# RGB_driver_main.net
KiCad netlist of a schematic drawn in EAGLE
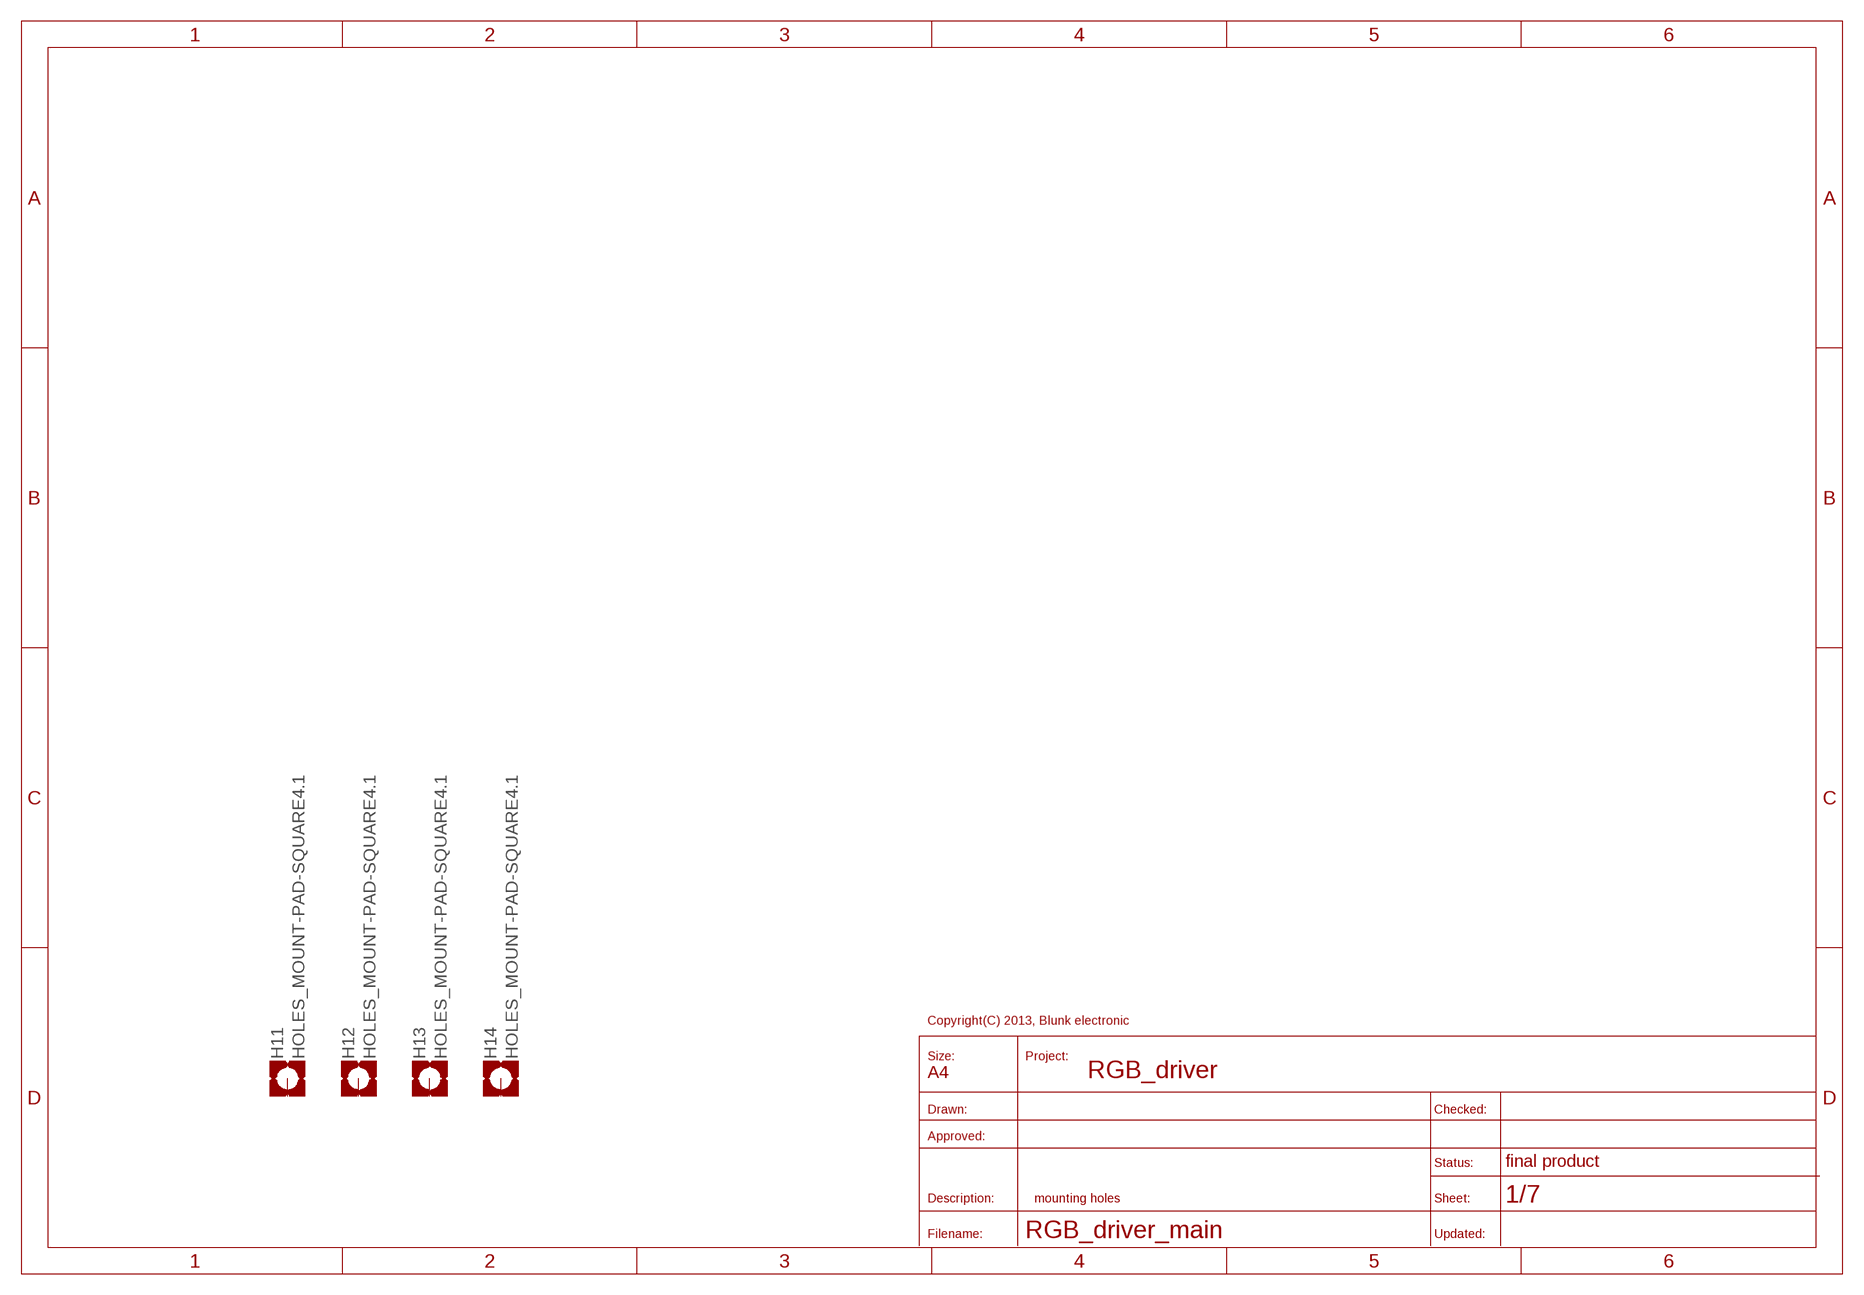
[diagram p0: schematic, sheet 1]
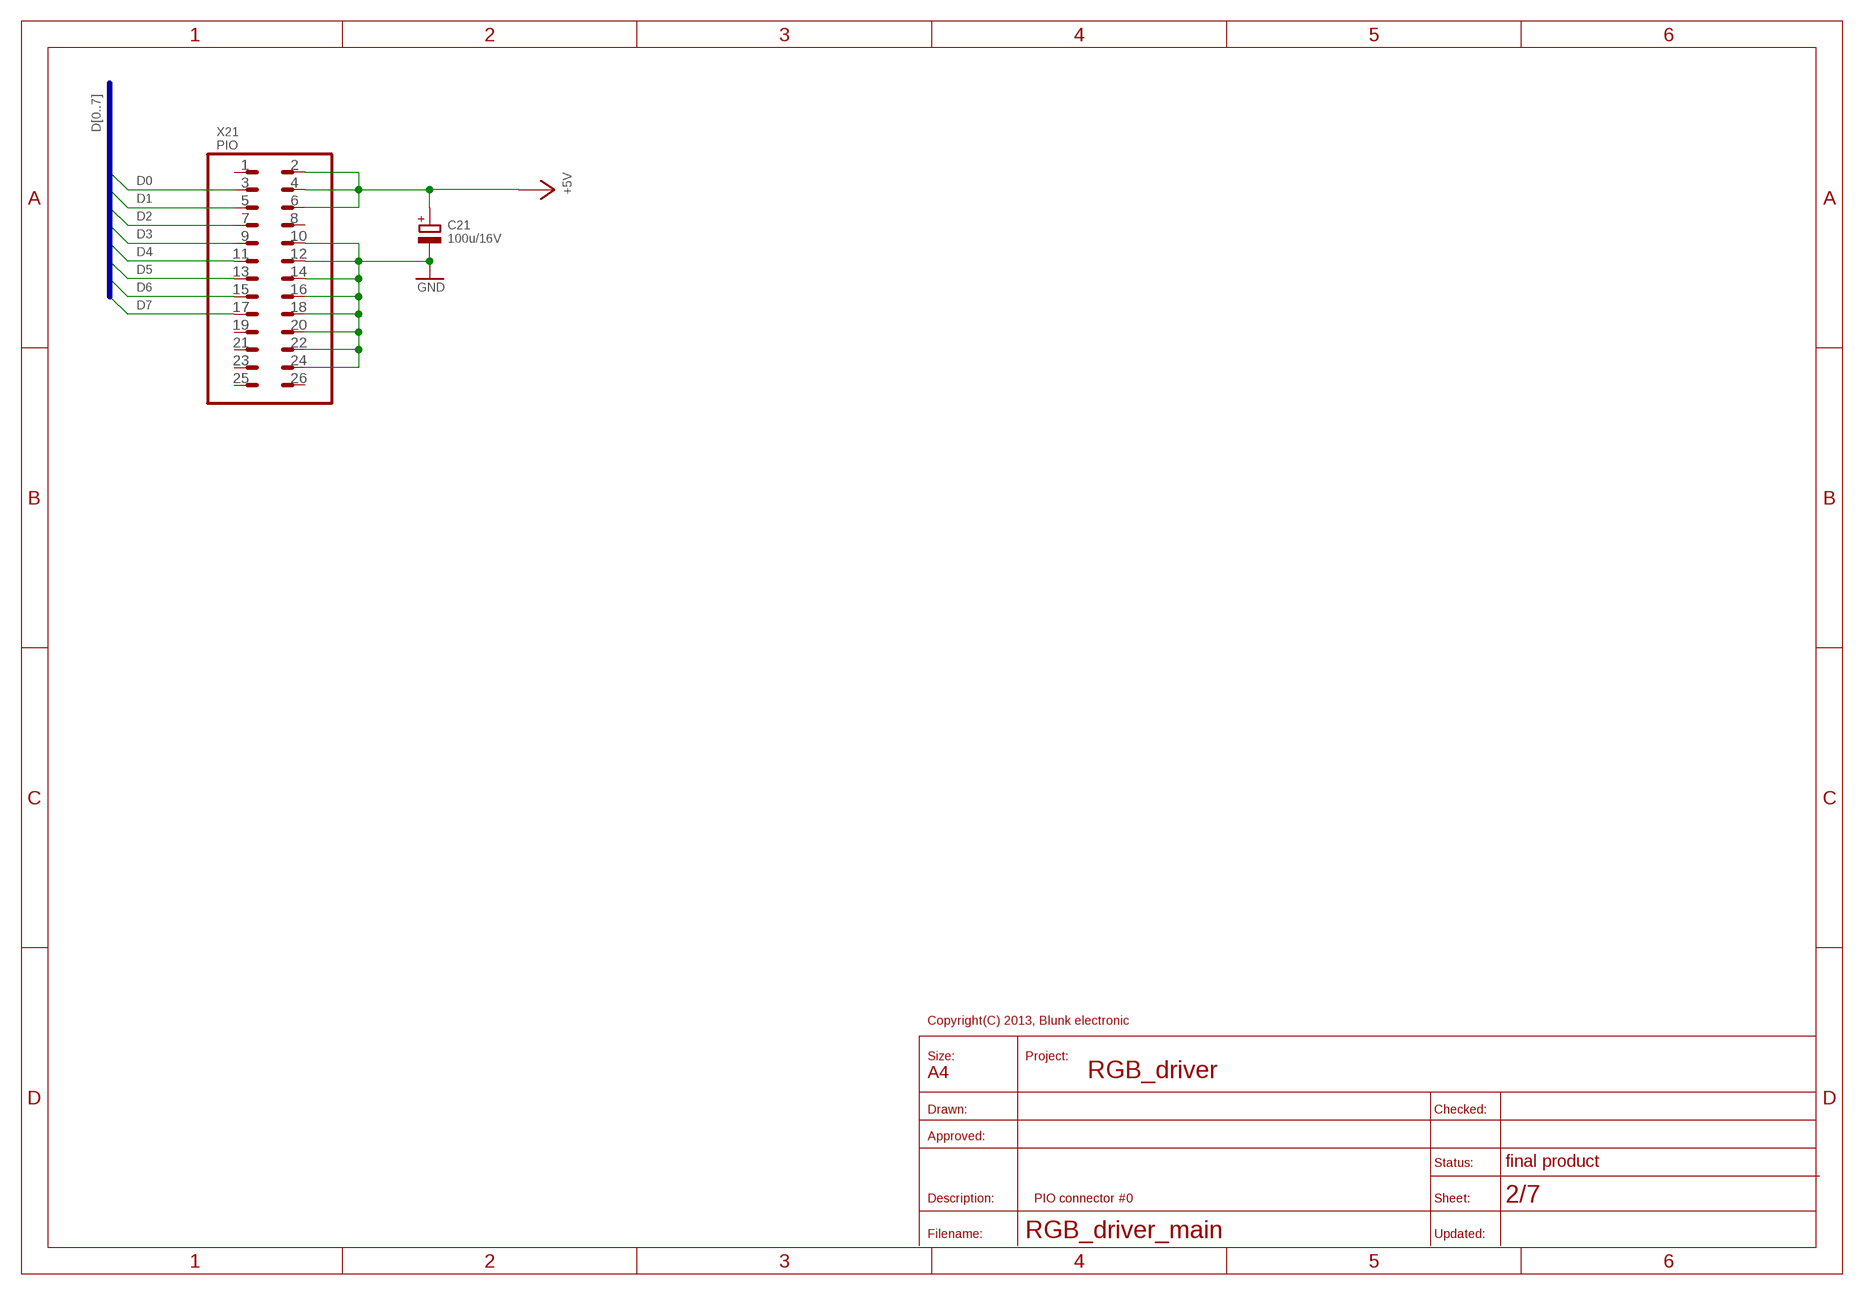
[diagram p1: schematic, sheet 2]
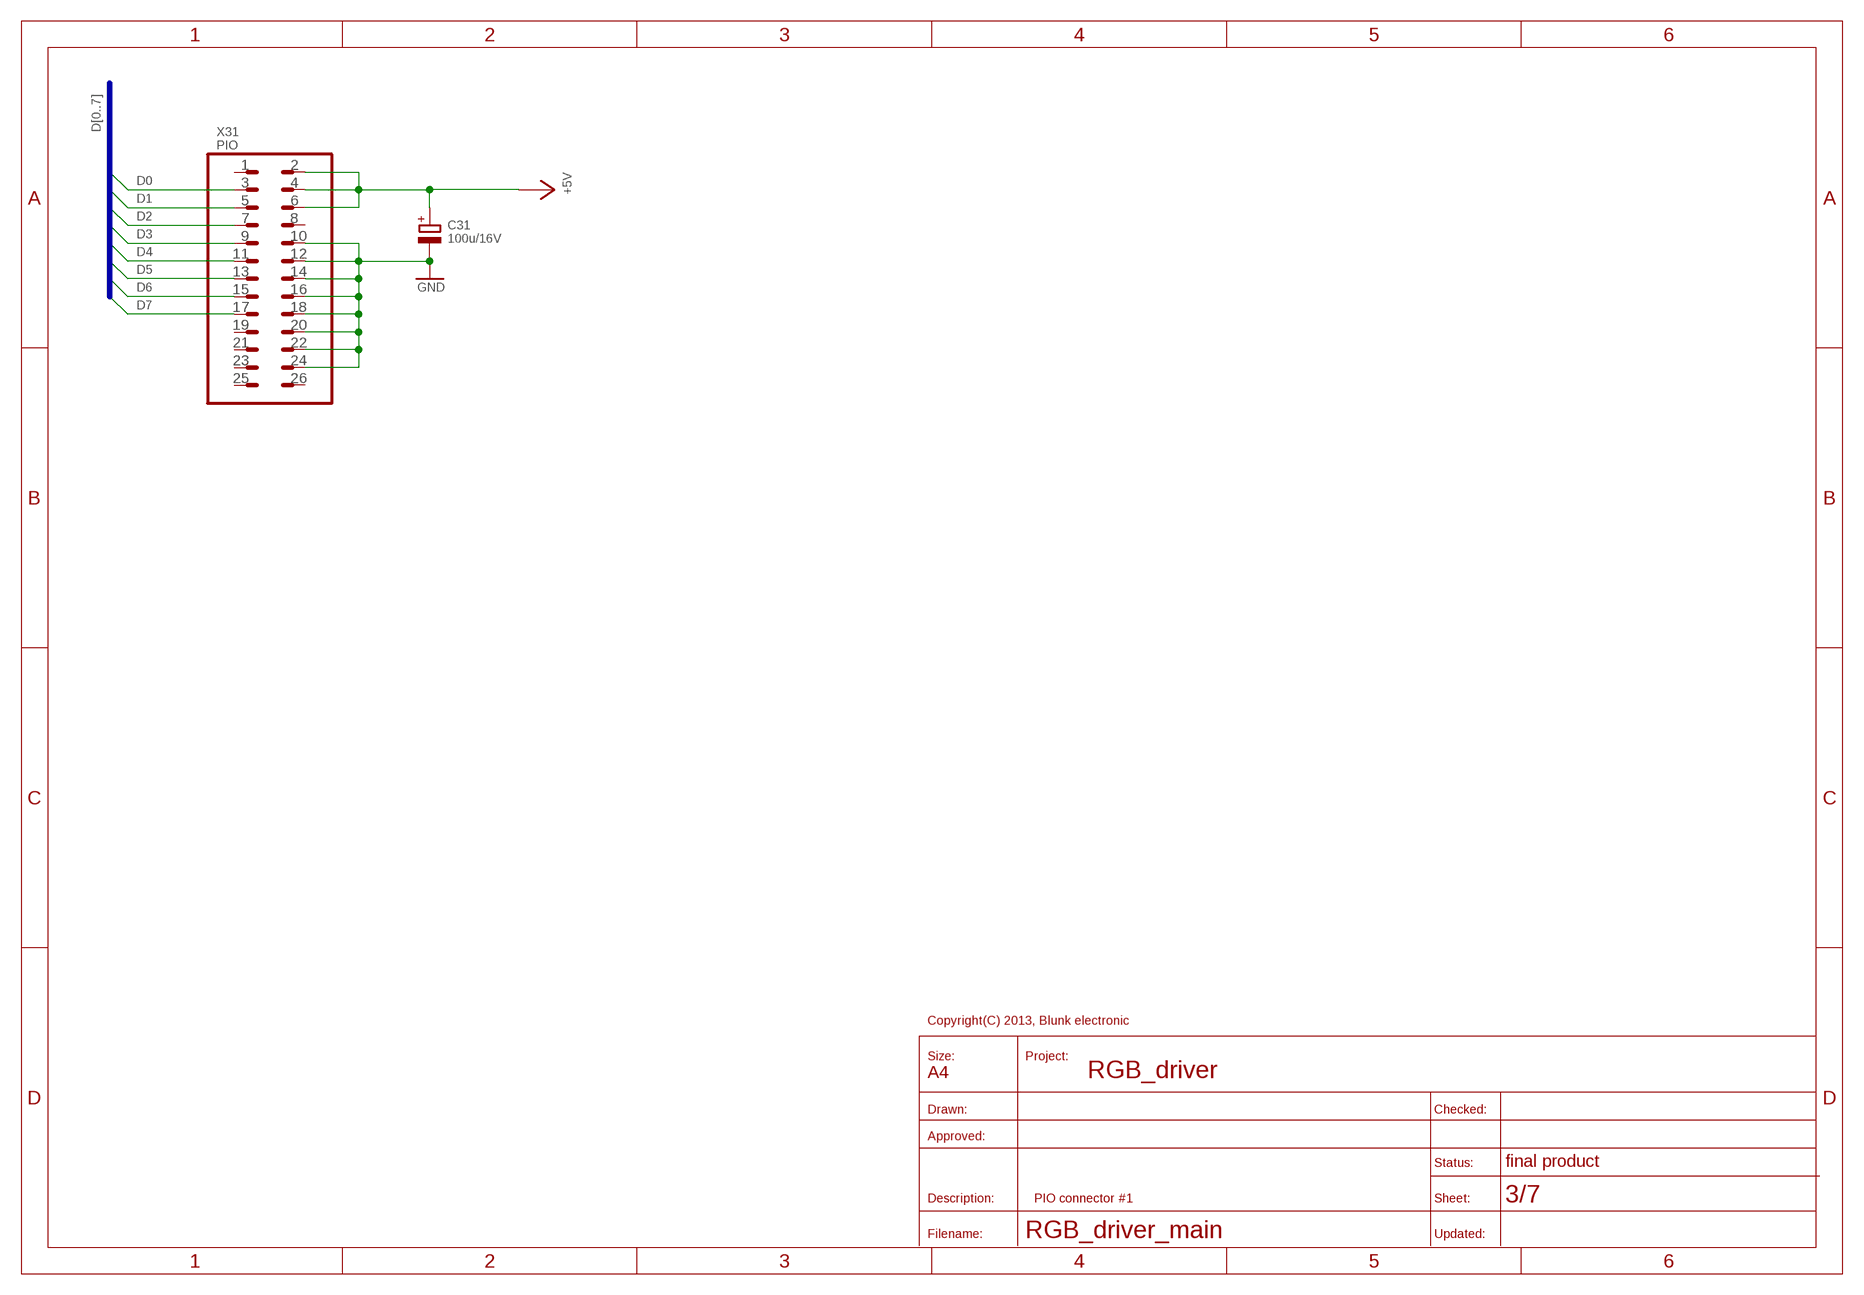
[diagram p2: schematic, sheet 3]
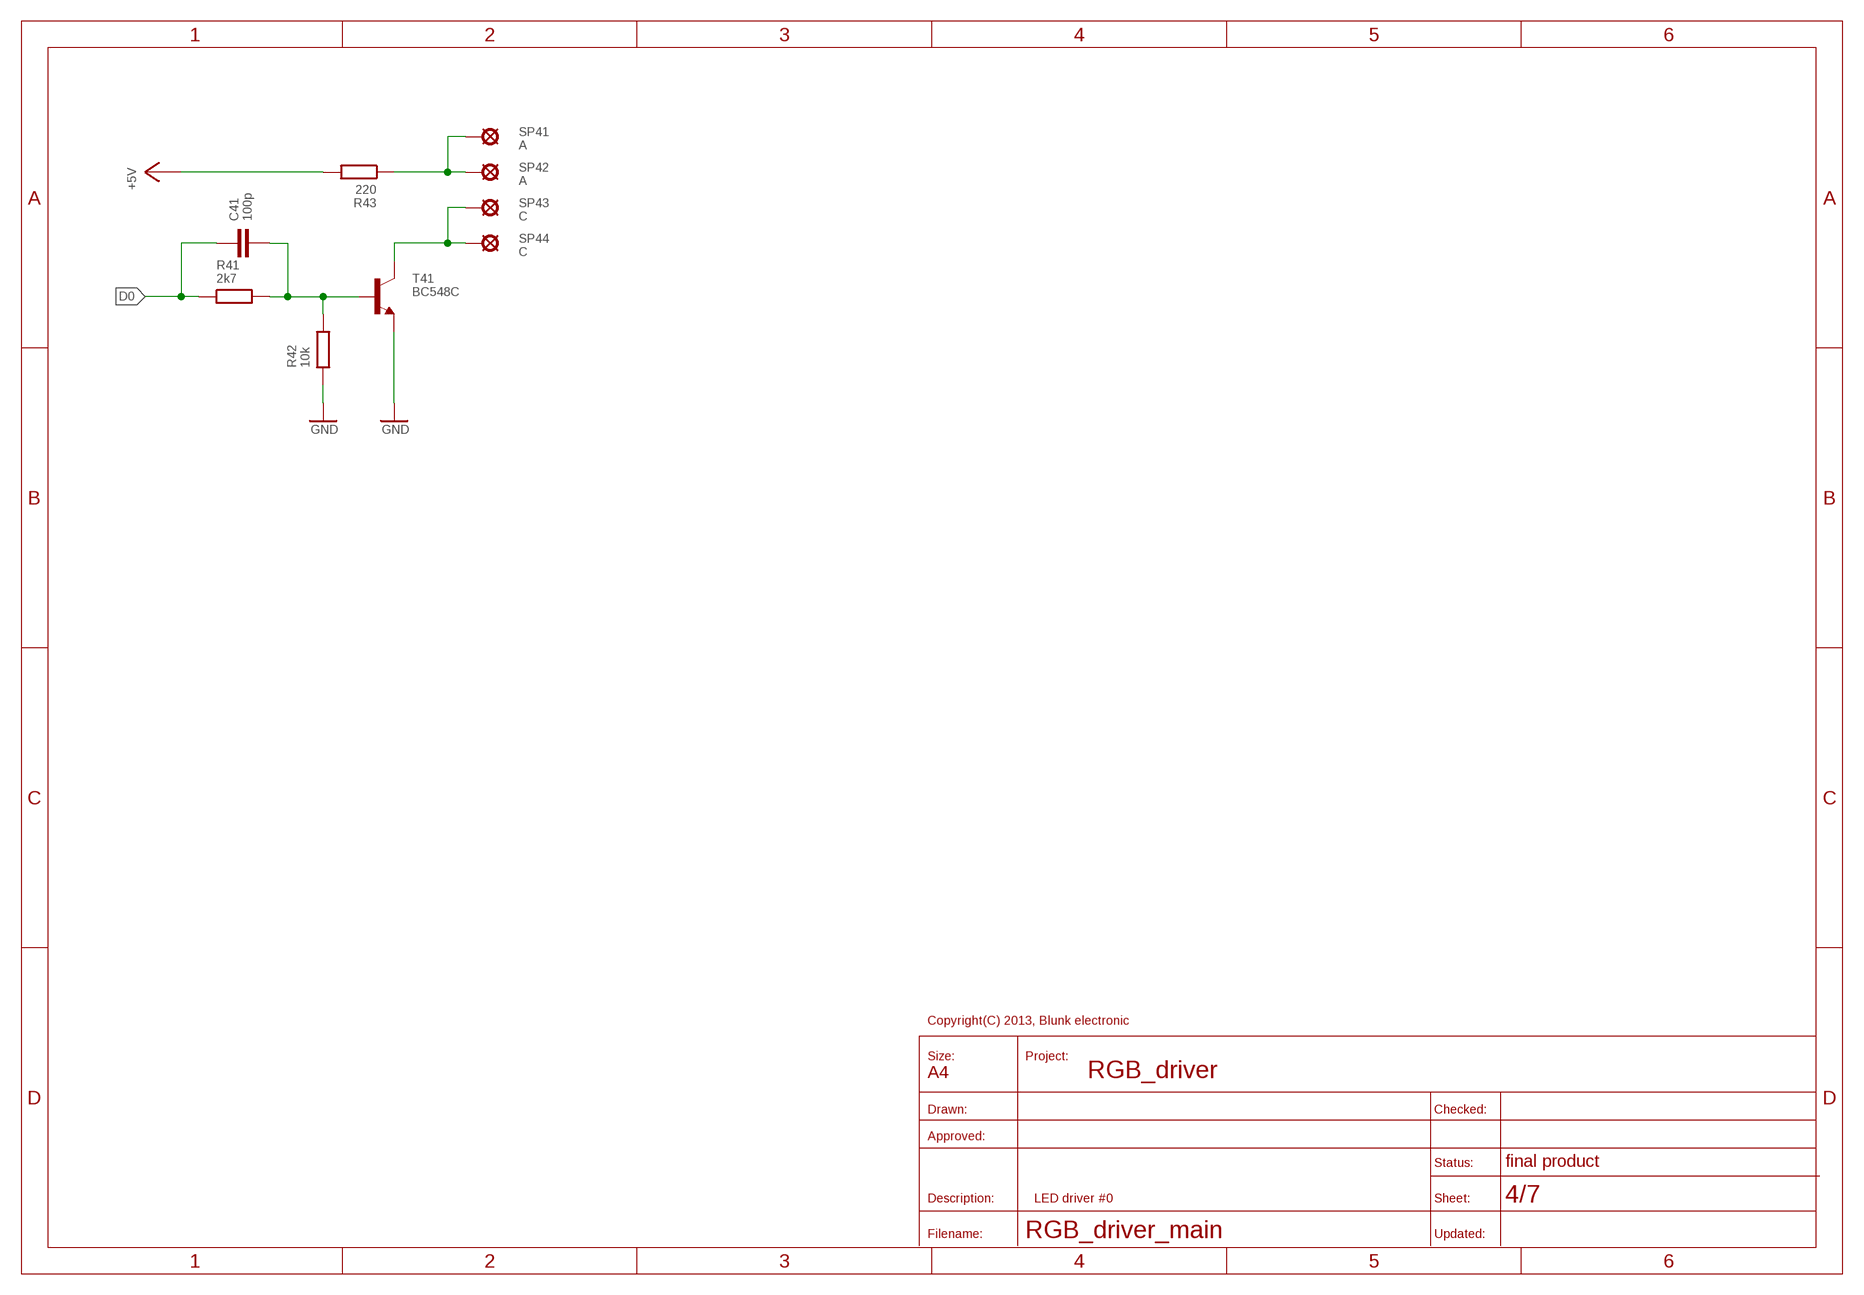
[diagram p3: schematic, sheet 4]
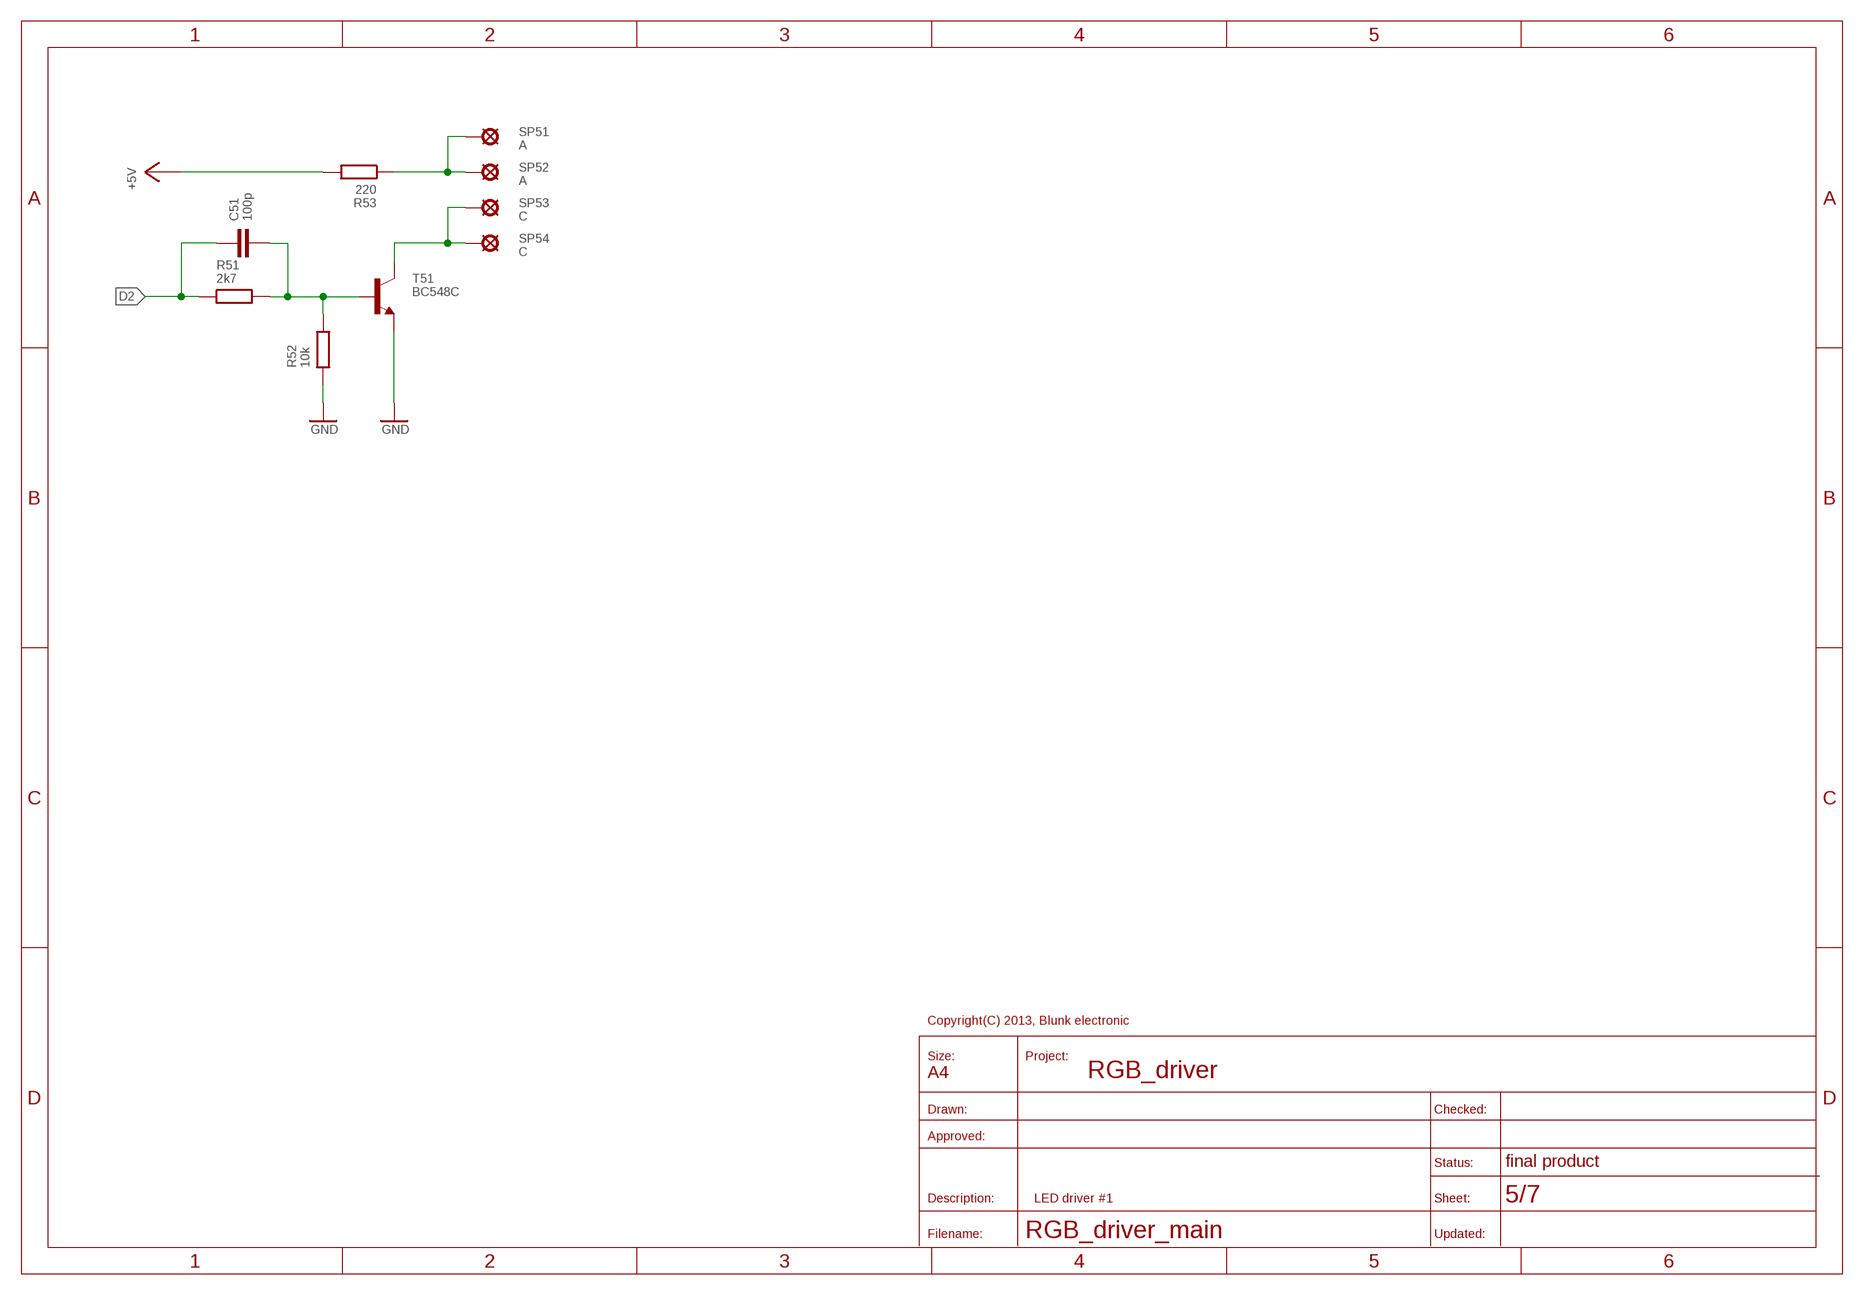
[diagram p4: schematic, sheet 5]
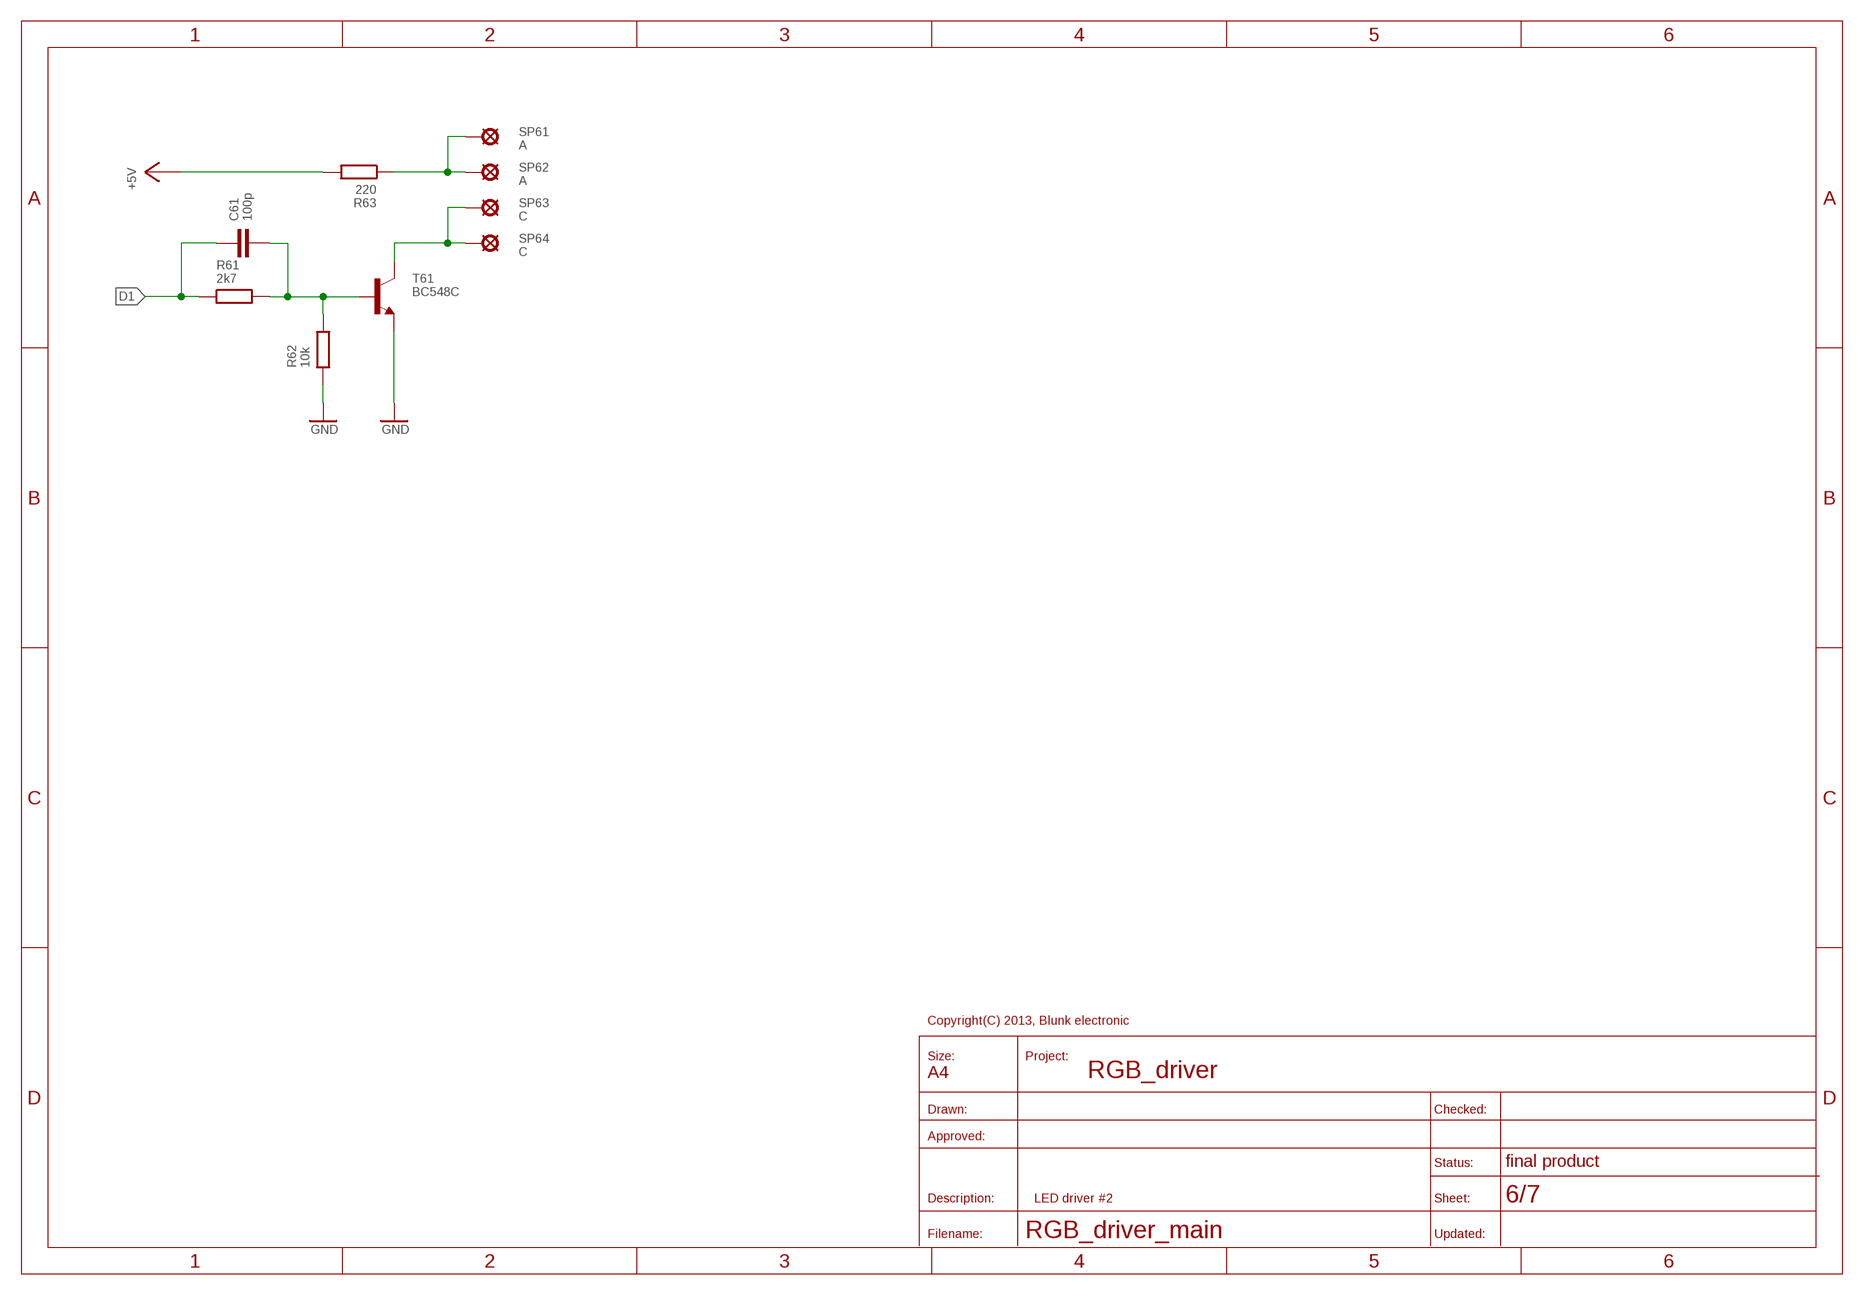
[diagram p5: schematic, sheet 6]
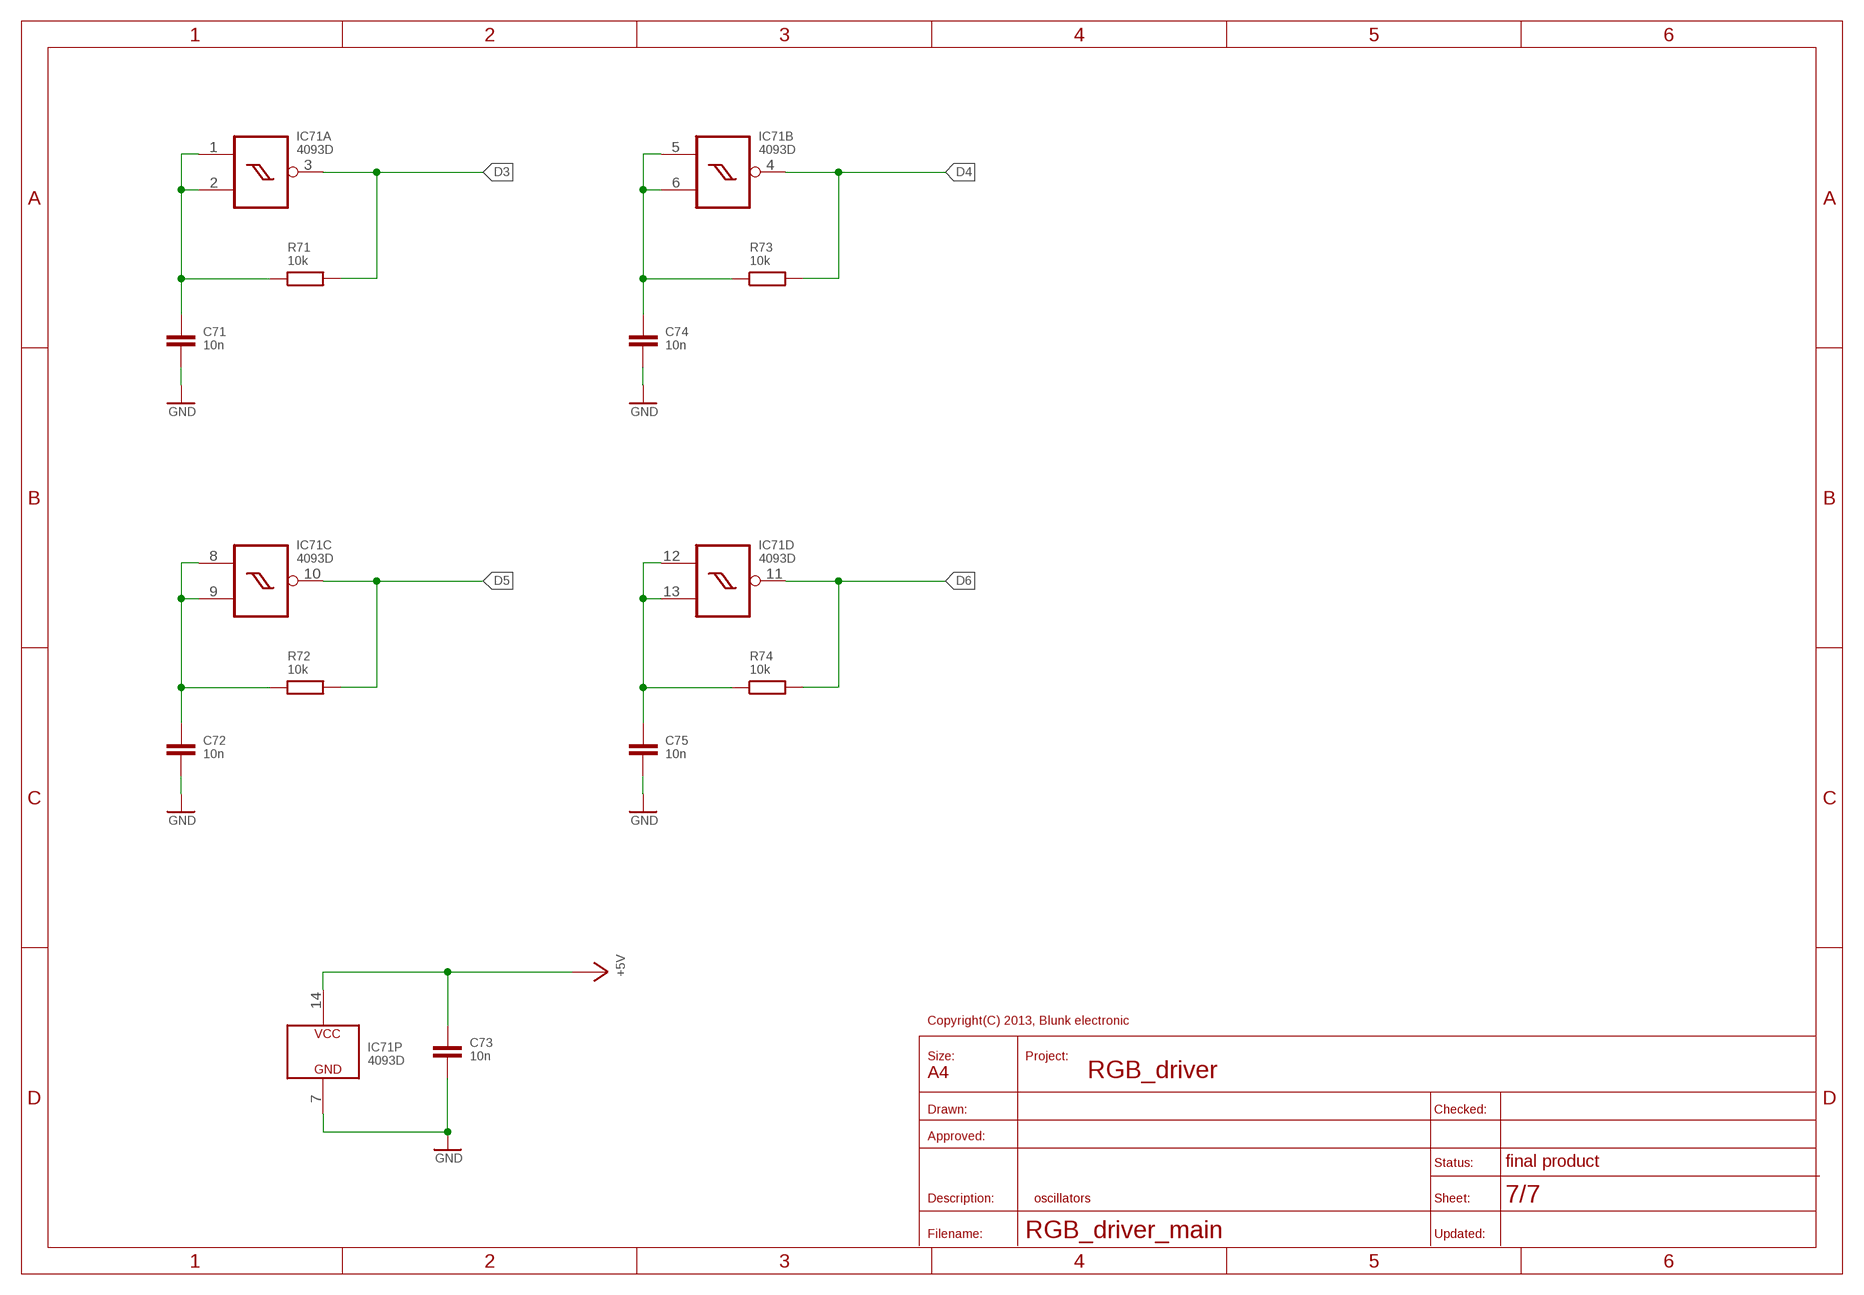
[diagram p6: schematic, sheet 7]

(export (version "E")
  (design (tool "Eeschema 10.0.6"))
  (components
    (comp (ref "C21")
      (value "100u/16V")
      (footprint "eagle-import:T_D7_2.54")
      (libsource (lib "eagle-import") (part "C_POL_EU_T_D7/2.54"))
    )
    (comp (ref "X21")
      (value "PIO")
      (footprint "eagle-import:T_PINHEAD_2X13-0")
      (libsource (lib "eagle-import") (part "MALE_2X13-T-0"))
    )
    (comp (ref "C61")
      (value "100p")
      (footprint "eagle-import:S_0805")
      (libsource (lib "eagle-import") (part "C_EU_S_0805"))
    )
    (comp (ref "R61")
      (value "2k7")
      (footprint "eagle-import:S_0805")
      (libsource (lib "eagle-import") (part "R_EU_S_0805"))
    )
    (comp (ref "R62")
      (value "10k")
      (footprint "eagle-import:S_0805")
      (libsource (lib "eagle-import") (part "R_EU_S_0805"))
    )
    (comp (ref "R63")
      (value "220")
      (footprint "eagle-import:S_0805")
      (libsource (lib "eagle-import") (part "R_EU_S_0805"))
    )
    (comp (ref "SP61")
      (value "A")
      (footprint "eagle-import:T_TEST_POINT_SMALL")
      (libsource (lib "eagle-import") (part "TEST_POINT-T-SMALL"))
    )
    (comp (ref "SP62")
      (value "A")
      (footprint "eagle-import:T_TEST_POINT_SMALL")
      (libsource (lib "eagle-import") (part "TEST_POINT-T-SMALL"))
    )
    (comp (ref "SP63")
      (value "C")
      (footprint "eagle-import:T_TEST_POINT_SMALL")
      (libsource (lib "eagle-import") (part "TEST_POINT-T-SMALL"))
    )
    (comp (ref "SP64")
      (value "C")
      (footprint "eagle-import:T_TEST_POINT_SMALL")
      (libsource (lib "eagle-import") (part "TEST_POINT-T-SMALL"))
    )
    (comp (ref "T61")
      (value "BC548C")
      (footprint "eagle-import:T_TO-92-CBE")
      (libsource (lib "eagle-import") (part "NPN"))
    )
    (comp (ref "C71")
      (value "10n")
      (footprint "eagle-import:S_0805")
      (libsource (lib "eagle-import") (part "C_EU_S_0805"))
    )
    (comp (ref "C72")
      (value "10n")
      (footprint "eagle-import:S_0805")
      (libsource (lib "eagle-import") (part "C_EU_S_0805"))
    )
    (comp (ref "C73")
      (value "10n")
      (footprint "eagle-import:S_0805")
      (libsource (lib "eagle-import") (part "C_EU_S_0805"))
    )
    (comp (ref "C74")
      (value "10n")
      (footprint "eagle-import:S_0805")
      (libsource (lib "eagle-import") (part "C_EU_S_0805"))
    )
    (comp (ref "C75")
      (value "10n")
      (footprint "eagle-import:S_0805")
      (libsource (lib "eagle-import") (part "C_EU_S_0805"))
    )
    (comp (ref "IC71")
      (value "4093D")
      (footprint "eagle-import:S_SO14")
      (libsource (lib "eagle-import") (part "4093D"))
    )
    (comp (ref "R71")
      (value "10k")
      (footprint "eagle-import:S_0805")
      (libsource (lib "eagle-import") (part "R_EU_S_0805"))
    )
    (comp (ref "R72")
      (value "10k")
      (footprint "eagle-import:S_0805")
      (libsource (lib "eagle-import") (part "R_EU_S_0805"))
    )
    (comp (ref "R73")
      (value "10k")
      (footprint "eagle-import:S_0805")
      (libsource (lib "eagle-import") (part "R_EU_S_0805"))
    )
    (comp (ref "R74")
      (value "10k")
      (footprint "eagle-import:S_0805")
      (libsource (lib "eagle-import") (part "R_EU_S_0805"))
    )
    (comp (ref "H11")
      (value "HOLES_MOUNT-PAD-SQUARE4.1")
      (footprint "eagle-import:HOLES_4,1-PAD-SQUARE")
      (libsource (lib "eagle-import") (part "HOLES_MOUNT-PAD-SQUARE4.1"))
    )
    (comp (ref "H12")
      (value "HOLES_MOUNT-PAD-SQUARE4.1")
      (footprint "eagle-import:HOLES_4,1-PAD-SQUARE")
      (libsource (lib "eagle-import") (part "HOLES_MOUNT-PAD-SQUARE4.1"))
    )
    (comp (ref "H13")
      (value "HOLES_MOUNT-PAD-SQUARE4.1")
      (footprint "eagle-import:HOLES_4,1-PAD-SQUARE")
      (libsource (lib "eagle-import") (part "HOLES_MOUNT-PAD-SQUARE4.1"))
    )
    (comp (ref "H14")
      (value "HOLES_MOUNT-PAD-SQUARE4.1")
      (footprint "eagle-import:HOLES_4,1-PAD-SQUARE")
      (libsource (lib "eagle-import") (part "HOLES_MOUNT-PAD-SQUARE4.1"))
    )
    (comp (ref "C41")
      (value "100p")
      (footprint "eagle-import:S_0805")
      (libsource (lib "eagle-import") (part "C_EU_S_0805"))
    )
    (comp (ref "R41")
      (value "2k7")
      (footprint "eagle-import:S_0805")
      (libsource (lib "eagle-import") (part "R_EU_S_0805"))
    )
    (comp (ref "R42")
      (value "10k")
      (footprint "eagle-import:S_0805")
      (libsource (lib "eagle-import") (part "R_EU_S_0805"))
    )
    (comp (ref "R43")
      (value "220")
      (footprint "eagle-import:S_0805")
      (libsource (lib "eagle-import") (part "R_EU_S_0805"))
    )
    (comp (ref "SP41")
      (value "A")
      (footprint "eagle-import:T_TEST_POINT_SMALL")
      (libsource (lib "eagle-import") (part "TEST_POINT-T-SMALL"))
    )
    (comp (ref "SP42")
      (value "A")
      (footprint "eagle-import:T_TEST_POINT_SMALL")
      (libsource (lib "eagle-import") (part "TEST_POINT-T-SMALL"))
    )
    (comp (ref "SP43")
      (value "C")
      (footprint "eagle-import:T_TEST_POINT_SMALL")
      (libsource (lib "eagle-import") (part "TEST_POINT-T-SMALL"))
    )
    (comp (ref "SP44")
      (value "C")
      (footprint "eagle-import:T_TEST_POINT_SMALL")
      (libsource (lib "eagle-import") (part "TEST_POINT-T-SMALL"))
    )
    (comp (ref "T41")
      (value "BC548C")
      (footprint "eagle-import:T_TO-92-CBE")
      (libsource (lib "eagle-import") (part "NPN"))
    )
    (comp (ref "C31")
      (value "100u/16V")
      (footprint "eagle-import:T_D7_2.54")
      (libsource (lib "eagle-import") (part "C_POL_EU_T_D7/2.54"))
    )
    (comp (ref "X31")
      (value "PIO")
      (footprint "eagle-import:T_PINHEAD_2X13-0")
      (libsource (lib "eagle-import") (part "MALE_2X13-T-0"))
    )
    (comp (ref "C51")
      (value "100p")
      (footprint "eagle-import:S_0805")
      (libsource (lib "eagle-import") (part "C_EU_S_0805"))
    )
    (comp (ref "R51")
      (value "2k7")
      (footprint "eagle-import:S_0805")
      (libsource (lib "eagle-import") (part "R_EU_S_0805"))
    )
    (comp (ref "R52")
      (value "10k")
      (footprint "eagle-import:S_0805")
      (libsource (lib "eagle-import") (part "R_EU_S_0805"))
    )
    (comp (ref "R53")
      (value "220")
      (footprint "eagle-import:S_0805")
      (libsource (lib "eagle-import") (part "R_EU_S_0805"))
    )
    (comp (ref "SP51")
      (value "A")
      (footprint "eagle-import:T_TEST_POINT_SMALL")
      (libsource (lib "eagle-import") (part "TEST_POINT-T-SMALL"))
    )
    (comp (ref "SP52")
      (value "A")
      (footprint "eagle-import:T_TEST_POINT_SMALL")
      (libsource (lib "eagle-import") (part "TEST_POINT-T-SMALL"))
    )
    (comp (ref "SP53")
      (value "C")
      (footprint "eagle-import:T_TEST_POINT_SMALL")
      (libsource (lib "eagle-import") (part "TEST_POINT-T-SMALL"))
    )
    (comp (ref "SP54")
      (value "C")
      (footprint "eagle-import:T_TEST_POINT_SMALL")
      (libsource (lib "eagle-import") (part "TEST_POINT-T-SMALL"))
    )
    (comp (ref "T51")
      (value "BC548C")
      (footprint "eagle-import:T_TO-92-CBE")
      (libsource (lib "eagle-import") (part "NPN"))
    )
  )
  (nets
    (net (code "1") (name "+5V") (class "Default")
      (node (ref "C21") (pin "+") (pinfunction "+_+") (pintype "passive"))
      (node (ref "C31") (pin "+") (pinfunction "+_+") (pintype "passive"))
      (node (ref "C73") (pin "1") (pinfunction "1_1") (pintype "passive"))
      (node (ref "IC71") (pin "14") (pinfunction "VCC_14") (pintype "power_in"))
      (node (ref "R43") (pin "2") (pinfunction "2_2") (pintype "passive"))
      (node (ref "R53") (pin "2") (pinfunction "2_2") (pintype "passive"))
      (node (ref "R63") (pin "2") (pinfunction "2_2") (pintype "passive"))
      (node (ref "X21") (pin "2") (pinfunction "2_2") (pintype "passive"))
      (node (ref "X21") (pin "4") (pinfunction "4_4") (pintype "passive"))
      (node (ref "X21") (pin "6") (pinfunction "6_6") (pintype "passive"))
      (node (ref "X31") (pin "2") (pinfunction "2_2") (pintype "passive"))
      (node (ref "X31") (pin "4") (pinfunction "4_4") (pintype "passive"))
      (node (ref "X31") (pin "6") (pinfunction "6_6") (pintype "passive"))
    )
    (net (code "4") (name "D0") (class "Default")
      (node (ref "C41") (pin "1") (pinfunction "1_1") (pintype "passive"))
      (node (ref "R41") (pin "1") (pinfunction "1_1") (pintype "passive"))
      (node (ref "X21") (pin "3") (pinfunction "3_3") (pintype "passive"))
      (node (ref "X31") (pin "3") (pinfunction "3_3") (pintype "passive"))
    )
    (net (code "5") (name "D1") (class "Default")
      (node (ref "C61") (pin "1") (pinfunction "1_1") (pintype "passive"))
      (node (ref "R61") (pin "1") (pinfunction "1_1") (pintype "passive"))
      (node (ref "X21") (pin "5") (pinfunction "5_5") (pintype "passive"))
      (node (ref "X31") (pin "5") (pinfunction "5_5") (pintype "passive"))
    )
    (net (code "6") (name "D2") (class "Default")
      (node (ref "C51") (pin "1") (pinfunction "1_1") (pintype "passive"))
      (node (ref "R51") (pin "1") (pinfunction "1_1") (pintype "passive"))
      (node (ref "X21") (pin "7") (pinfunction "7_7") (pintype "passive"))
      (node (ref "X31") (pin "7") (pinfunction "7_7") (pintype "passive"))
    )
    (net (code "7") (name "D3") (class "Default")
      (node (ref "IC71") (pin "3") (pinfunction "O_3") (pintype "output"))
      (node (ref "R71") (pin "2") (pinfunction "2_2") (pintype "passive"))
      (node (ref "X21") (pin "9") (pinfunction "9_9") (pintype "passive"))
      (node (ref "X31") (pin "9") (pinfunction "9_9") (pintype "passive"))
    )
    (net (code "8") (name "D4") (class "Default")
      (node (ref "IC71") (pin "4") (pinfunction "O_4") (pintype "output"))
      (node (ref "R73") (pin "2") (pinfunction "2_2") (pintype "passive"))
      (node (ref "X21") (pin "11") (pinfunction "11_11") (pintype "passive"))
      (node (ref "X31") (pin "11") (pinfunction "11_11") (pintype "passive"))
    )
    (net (code "9") (name "D5") (class "Default")
      (node (ref "IC71") (pin "10") (pinfunction "O_10") (pintype "output"))
      (node (ref "R72") (pin "2") (pinfunction "2_2") (pintype "passive"))
      (node (ref "X21") (pin "13") (pinfunction "13_13") (pintype "passive"))
      (node (ref "X31") (pin "13") (pinfunction "13_13") (pintype "passive"))
    )
    (net (code "10") (name "D6") (class "Default")
      (node (ref "IC71") (pin "11") (pinfunction "O_11") (pintype "output"))
      (node (ref "R74") (pin "2") (pinfunction "2_2") (pintype "passive"))
      (node (ref "X21") (pin "15") (pinfunction "15_15") (pintype "passive"))
      (node (ref "X31") (pin "15") (pinfunction "15_15") (pintype "passive"))
    )
    (net (code "11") (name "D7") (class "Default")
      (node (ref "X21") (pin "17") (pinfunction "17_17") (pintype "passive"))
      (node (ref "X31") (pin "17") (pinfunction "17_17") (pintype "passive"))
    )
    (net (code "12") (name "GND") (class "Default")
      (node (ref "C21") (pin "-") (pinfunction "-_-") (pintype "passive"))
      (node (ref "C31") (pin "-") (pinfunction "-_-") (pintype "passive"))
      (node (ref "C71") (pin "2") (pinfunction "2_2") (pintype "passive"))
      (node (ref "C72") (pin "2") (pinfunction "2_2") (pintype "passive"))
      (node (ref "C73") (pin "2") (pinfunction "2_2") (pintype "passive"))
      (node (ref "C74") (pin "2") (pinfunction "2_2") (pintype "passive"))
      (node (ref "C75") (pin "2") (pinfunction "2_2") (pintype "passive"))
      (node (ref "IC71") (pin "7") (pinfunction "GND_7") (pintype "power_in"))
      (node (ref "R42") (pin "1") (pinfunction "1_1") (pintype "passive"))
      (node (ref "R52") (pin "1") (pinfunction "1_1") (pintype "passive"))
      (node (ref "R62") (pin "1") (pinfunction "1_1") (pintype "passive"))
      (node (ref "T41") (pin "E") (pinfunction "E_E") (pintype "passive"))
      (node (ref "T51") (pin "E") (pinfunction "E_E") (pintype "passive"))
      (node (ref "T61") (pin "E") (pinfunction "E_E") (pintype "passive"))
      (node (ref "X21") (pin "10") (pinfunction "10_10") (pintype "passive"))
      (node (ref "X21") (pin "12") (pinfunction "12_12") (pintype "passive"))
      (node (ref "X21") (pin "14") (pinfunction "14_14") (pintype "passive"))
      (node (ref "X21") (pin "16") (pinfunction "16_16") (pintype "passive"))
      (node (ref "X21") (pin "18") (pinfunction "18_18") (pintype "passive"))
      (node (ref "X21") (pin "20") (pinfunction "20_20") (pintype "passive"))
      (node (ref "X21") (pin "22") (pinfunction "22_22") (pintype "passive"))
      (node (ref "X21") (pin "24") (pinfunction "24_24") (pintype "passive"))
      (node (ref "X31") (pin "10") (pinfunction "10_10") (pintype "passive"))
      (node (ref "X31") (pin "12") (pinfunction "12_12") (pintype "passive"))
      (node (ref "X31") (pin "14") (pinfunction "14_14") (pintype "passive"))
      (node (ref "X31") (pin "16") (pinfunction "16_16") (pintype "passive"))
      (node (ref "X31") (pin "18") (pinfunction "18_18") (pintype "passive"))
      (node (ref "X31") (pin "20") (pinfunction "20_20") (pintype "passive"))
      (node (ref "X31") (pin "22") (pinfunction "22_22") (pintype "passive"))
      (node (ref "X31") (pin "24") (pinfunction "24_24") (pintype "passive"))
    )
    (net (code "13") (name "Net-(C41-Pad2)") (class "Default")
      (node (ref "C41") (pin "2") (pinfunction "2_2") (pintype "passive"))
      (node (ref "R41") (pin "2") (pinfunction "2_2") (pintype "passive"))
      (node (ref "R42") (pin "2") (pinfunction "2_2") (pintype "passive"))
      (node (ref "T41") (pin "B") (pinfunction "B_B") (pintype "passive"))
    )
    (net (code "14") (name "Net-(C51-Pad2)") (class "Default")
      (node (ref "C51") (pin "2") (pinfunction "2_2") (pintype "passive"))
      (node (ref "R51") (pin "2") (pinfunction "2_2") (pintype "passive"))
      (node (ref "R52") (pin "2") (pinfunction "2_2") (pintype "passive"))
      (node (ref "T51") (pin "B") (pinfunction "B_B") (pintype "passive"))
    )
    (net (code "15") (name "Net-(C61-Pad2)") (class "Default")
      (node (ref "C61") (pin "2") (pinfunction "2_2") (pintype "passive"))
      (node (ref "R61") (pin "2") (pinfunction "2_2") (pintype "passive"))
      (node (ref "R62") (pin "2") (pinfunction "2_2") (pintype "passive"))
      (node (ref "T61") (pin "B") (pinfunction "B_B") (pintype "passive"))
    )
    (net (code "16") (name "Net-(IC71A-I0)") (class "Default")
      (node (ref "C71") (pin "1") (pinfunction "1_1") (pintype "passive"))
      (node (ref "IC71") (pin "1") (pinfunction "I0_1") (pintype "input"))
      (node (ref "IC71") (pin "2") (pinfunction "I1_2") (pintype "input"))
      (node (ref "R71") (pin "1") (pinfunction "1_1") (pintype "passive"))
    )
    (net (code "17") (name "Net-(IC71B-I0)") (class "Default")
      (node (ref "C74") (pin "1") (pinfunction "1_1") (pintype "passive"))
      (node (ref "IC71") (pin "5") (pinfunction "I0_5") (pintype "input"))
      (node (ref "IC71") (pin "6") (pinfunction "I1_6") (pintype "input"))
      (node (ref "R73") (pin "1") (pinfunction "1_1") (pintype "passive"))
    )
    (net (code "18") (name "Net-(IC71C-I0)") (class "Default")
      (node (ref "C72") (pin "1") (pinfunction "1_1") (pintype "passive"))
      (node (ref "IC71") (pin "8") (pinfunction "I0_8") (pintype "input"))
      (node (ref "IC71") (pin "9") (pinfunction "I1_9") (pintype "input"))
      (node (ref "R72") (pin "1") (pinfunction "1_1") (pintype "passive"))
    )
    (net (code "19") (name "Net-(IC71D-I0)") (class "Default")
      (node (ref "C75") (pin "1") (pinfunction "1_1") (pintype "passive"))
      (node (ref "IC71") (pin "12") (pinfunction "I0_12") (pintype "input"))
      (node (ref "IC71") (pin "13") (pinfunction "I1_13") (pintype "input"))
      (node (ref "R74") (pin "1") (pinfunction "1_1") (pintype "passive"))
    )
    (net (code "20") (name "Net-(SP41-MP)") (class "Default")
      (node (ref "R43") (pin "1") (pinfunction "1_1") (pintype "passive"))
      (node (ref "SP41") (pin "1") (pinfunction "MP_1") (pintype "passive"))
      (node (ref "SP42") (pin "1") (pinfunction "MP_1") (pintype "passive"))
    )
    (net (code "21") (name "Net-(SP43-MP)") (class "Default")
      (node (ref "SP43") (pin "1") (pinfunction "MP_1") (pintype "passive"))
      (node (ref "SP44") (pin "1") (pinfunction "MP_1") (pintype "passive"))
      (node (ref "T41") (pin "C") (pinfunction "C_C") (pintype "passive"))
    )
    (net (code "22") (name "Net-(SP51-MP)") (class "Default")
      (node (ref "R53") (pin "1") (pinfunction "1_1") (pintype "passive"))
      (node (ref "SP51") (pin "1") (pinfunction "MP_1") (pintype "passive"))
      (node (ref "SP52") (pin "1") (pinfunction "MP_1") (pintype "passive"))
    )
    (net (code "23") (name "Net-(SP53-MP)") (class "Default")
      (node (ref "SP53") (pin "1") (pinfunction "MP_1") (pintype "passive"))
      (node (ref "SP54") (pin "1") (pinfunction "MP_1") (pintype "passive"))
      (node (ref "T51") (pin "C") (pinfunction "C_C") (pintype "passive"))
    )
    (net (code "24") (name "Net-(SP61-MP)") (class "Default")
      (node (ref "R63") (pin "1") (pinfunction "1_1") (pintype "passive"))
      (node (ref "SP61") (pin "1") (pinfunction "MP_1") (pintype "passive"))
      (node (ref "SP62") (pin "1") (pinfunction "MP_1") (pintype "passive"))
    )
    (net (code "25") (name "Net-(SP63-MP)") (class "Default")
      (node (ref "SP63") (pin "1") (pinfunction "MP_1") (pintype "passive"))
      (node (ref "SP64") (pin "1") (pinfunction "MP_1") (pintype "passive"))
      (node (ref "T61") (pin "C") (pinfunction "C_C") (pintype "passive"))
    )
    (net (code "26") (name "unconnected-(H11-MOUNT-PadB4,1)") (class "Default")
      (node (ref "H11") (pin "B4,1") (pinfunction "MOUNT_B4,1") (pintype "passive"))
    )
    (net (code "27") (name "unconnected-(H12-MOUNT-PadB4,1)") (class "Default")
      (node (ref "H12") (pin "B4,1") (pinfunction "MOUNT_B4,1") (pintype "passive"))
    )
    (net (code "28") (name "unconnected-(H13-MOUNT-PadB4,1)") (class "Default")
      (node (ref "H13") (pin "B4,1") (pinfunction "MOUNT_B4,1") (pintype "passive"))
    )
    (net (code "29") (name "unconnected-(H14-MOUNT-PadB4,1)") (class "Default")
      (node (ref "H14") (pin "B4,1") (pinfunction "MOUNT_B4,1") (pintype "passive"))
    )
    (net (code "30") (name "unconnected-(X21-Pad1)") (class "Default")
      (node (ref "X21") (pin "1") (pinfunction "1_1") (pintype "passive"))
    )
    (net (code "31") (name "unconnected-(X21-Pad8)") (class "Default")
      (node (ref "X21") (pin "8") (pinfunction "8_8") (pintype "passive"))
    )
    (net (code "32") (name "unconnected-(X21-Pad19)") (class "Default")
      (node (ref "X21") (pin "19") (pinfunction "19_19") (pintype "passive"))
    )
    (net (code "33") (name "unconnected-(X21-Pad21)") (class "Default")
      (node (ref "X21") (pin "21") (pinfunction "21_21") (pintype "passive"))
    )
    (net (code "34") (name "unconnected-(X21-Pad23)") (class "Default")
      (node (ref "X21") (pin "23") (pinfunction "23_23") (pintype "passive"))
    )
    (net (code "35") (name "unconnected-(X21-Pad25)") (class "Default")
      (node (ref "X21") (pin "25") (pinfunction "25_25") (pintype "passive"))
    )
    (net (code "36") (name "unconnected-(X21-Pad26)") (class "Default")
      (node (ref "X21") (pin "26") (pinfunction "26_26") (pintype "passive"))
    )
    (net (code "37") (name "unconnected-(X31-Pad1)") (class "Default")
      (node (ref "X31") (pin "1") (pinfunction "1_1") (pintype "passive"))
    )
    (net (code "38") (name "unconnected-(X31-Pad8)") (class "Default")
      (node (ref "X31") (pin "8") (pinfunction "8_8") (pintype "passive"))
    )
    (net (code "39") (name "unconnected-(X31-Pad19)") (class "Default")
      (node (ref "X31") (pin "19") (pinfunction "19_19") (pintype "passive"))
    )
    (net (code "40") (name "unconnected-(X31-Pad21)") (class "Default")
      (node (ref "X31") (pin "21") (pinfunction "21_21") (pintype "passive"))
    )
    (net (code "41") (name "unconnected-(X31-Pad23)") (class "Default")
      (node (ref "X31") (pin "23") (pinfunction "23_23") (pintype "passive"))
    )
    (net (code "42") (name "unconnected-(X31-Pad25)") (class "Default")
      (node (ref "X31") (pin "25") (pinfunction "25_25") (pintype "passive"))
    )
    (net (code "43") (name "unconnected-(X31-Pad26)") (class "Default")
      (node (ref "X31") (pin "26") (pinfunction "26_26") (pintype "passive"))
    )
  )
)
